# H-00491_-_Top.net
KiCad netlist of a schematic drawn in Altium Designer
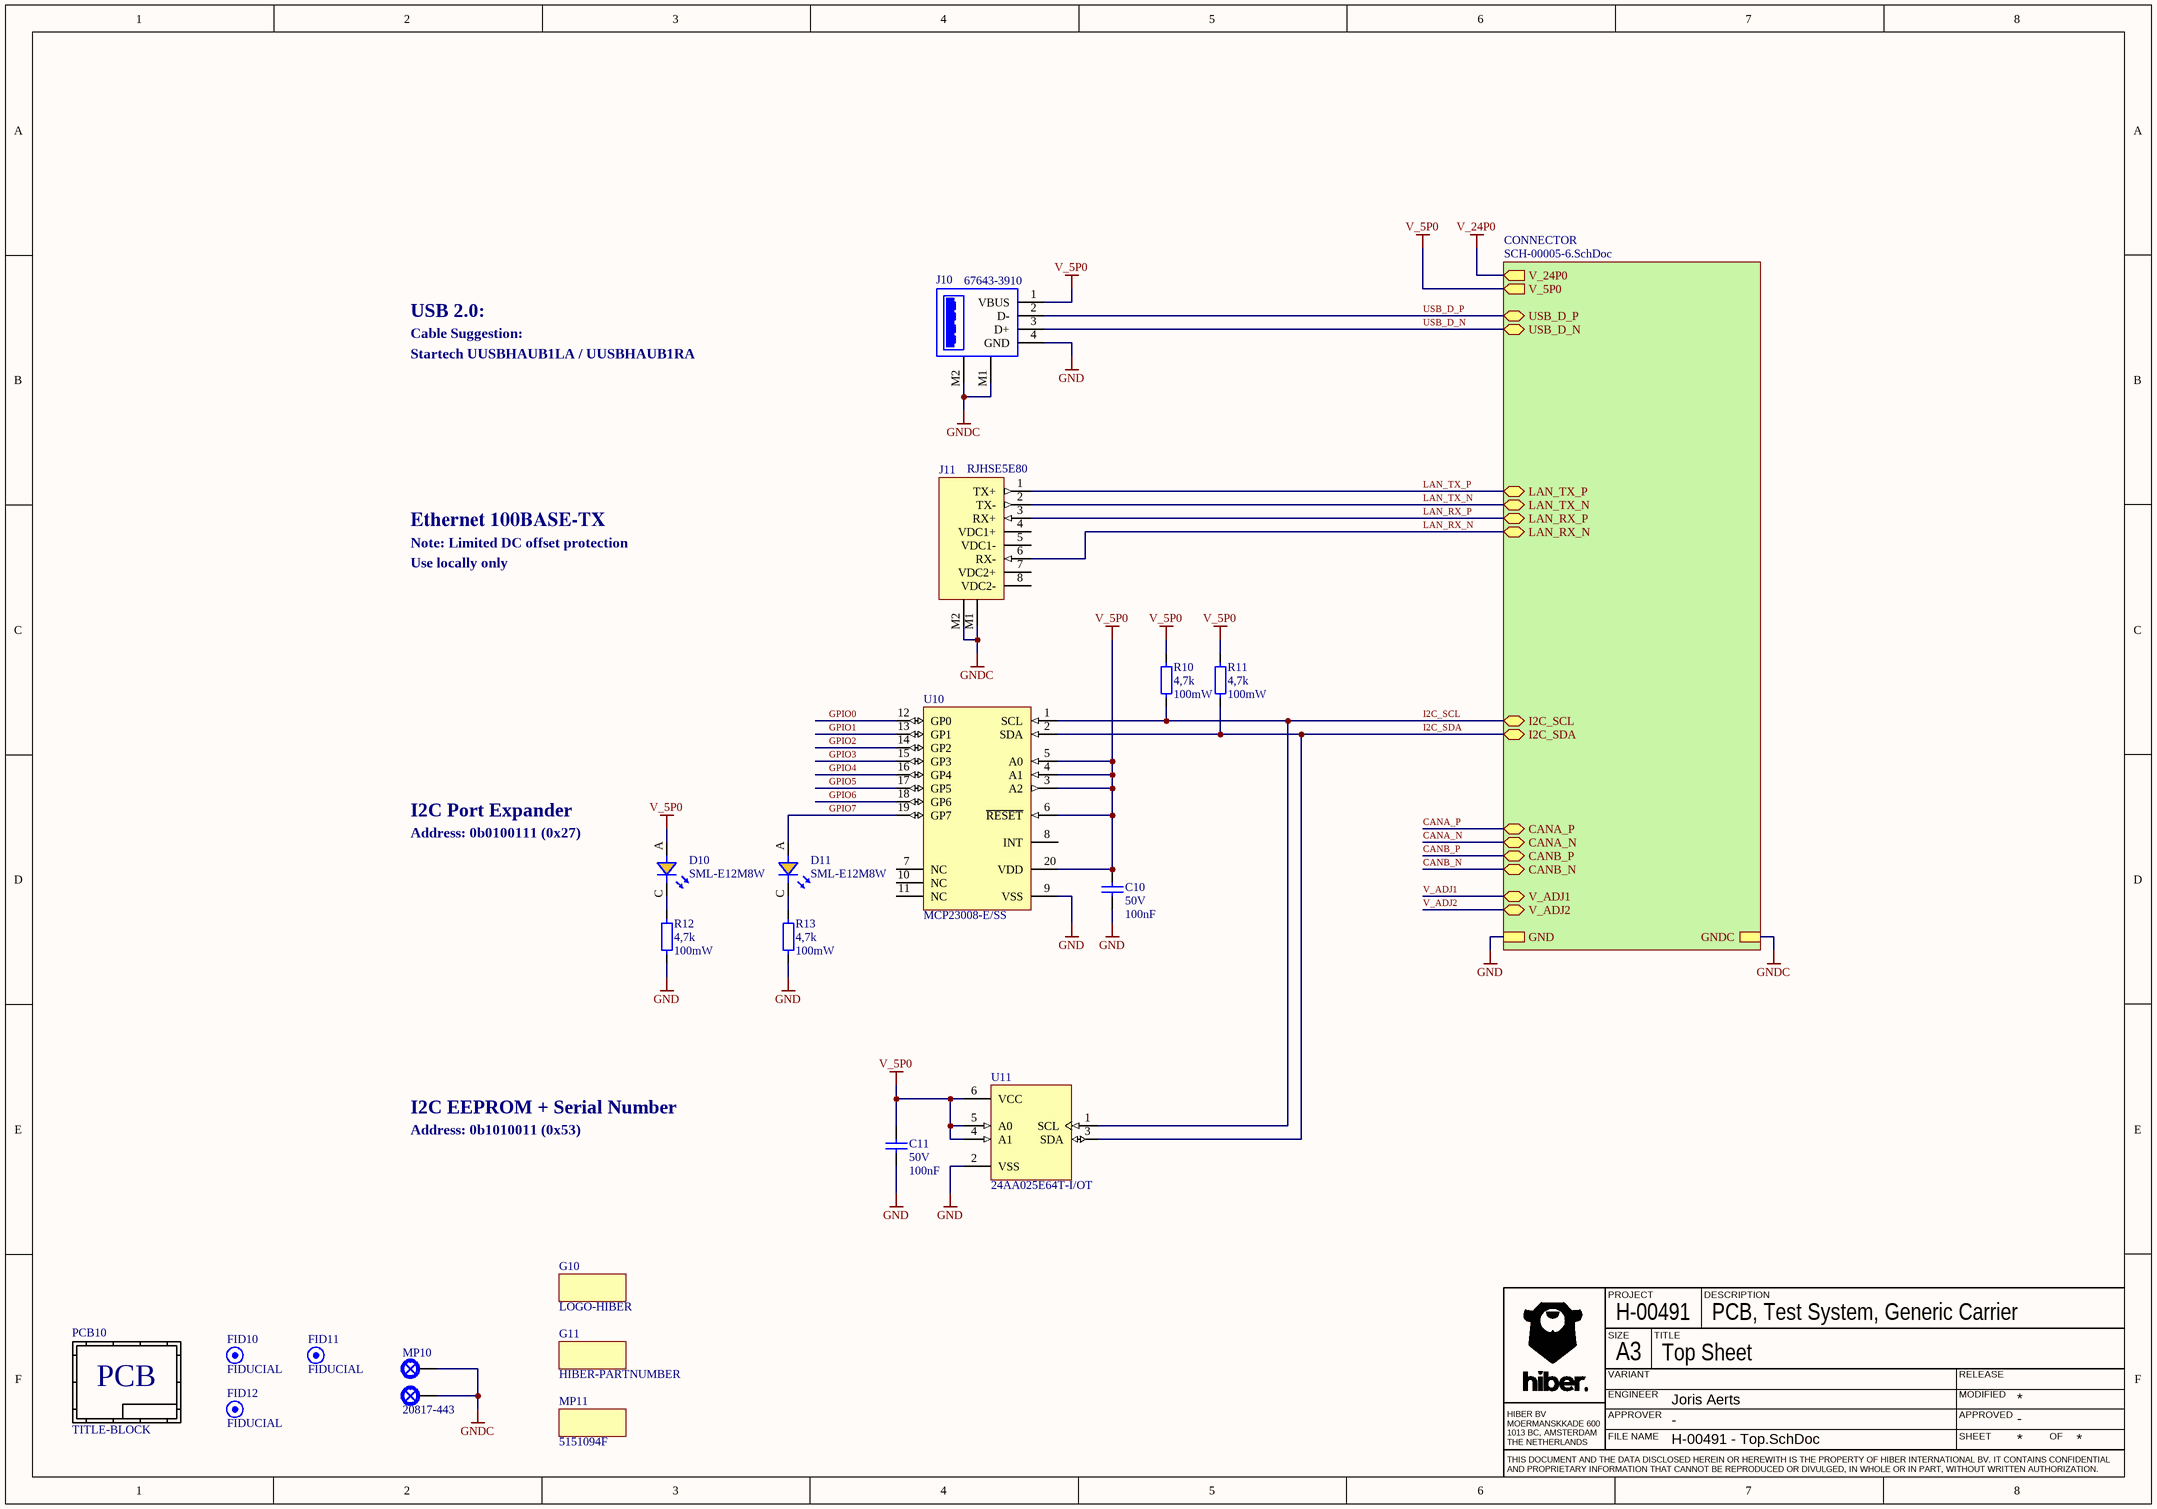
[diagram p0: H-00491 - Top.SchDoc]

(export (version "E")
  (design (tool "Eeschema 10.0.6"))
  (components
    (comp (ref "C10")
      (value "100nF")
      (footprint "CAPC160X80X87L35N")
      (description "CAP Standard 0603 (1608) 100,0nF 50V X7R (Standard)")
      (fields
        (field (name "RATED VOLTAGE") "50V")
        (field (name "TOLERANCE") "10%")
        (field (name "Comment") "C0603C104K5RACTU")
      )
      (libsource (lib "Hiber") (part "CAPACITOR"))
    )
    (comp (ref "C11")
      (value "100nF")
      (footprint "CAPC160X80X87L35N")
      (description "CAP Standard 0603 (1608) 100,0nF 50V X7R (Standard)")
      (fields
        (field (name "RATED VOLTAGE") "50V")
        (field (name "TOLERANCE") "10%")
        (field (name "Comment") "C0603C104K5RACTU")
      )
      (libsource (lib "Hiber") (part "CAPACITOR"))
    )
    (comp (ref "D10")
      (value "SML-E12M8W")
      (footprint "LEDC170X80X80L20_YELLOW")
      (description "LED Yellowish green Diffused 0603 SMD")
      (libsource (lib "Hiber") (part "DIODE-LED-YELLOW"))
    )
    (comp (ref "D11")
      (value "SML-E12M8W")
      (footprint "LEDC170X80X80L20_YELLOW")
      (description "LED Yellowish green Diffused 0603 SMD")
      (libsource (lib "Hiber") (part "DIODE-LED-YELLOW"))
    )
    (comp (ref "FID10")
      (value "FIDUCIAL")
      (footprint "FIDUCIAL_075X150")
      (description "Fiducial")
      (libsource (lib "Hiber Vault") (part "FIDUCIAL"))
    )
    (comp (ref "FID11")
      (value "FIDUCIAL")
      (footprint "FIDUCIAL_075X150")
      (description "Fiducial")
      (libsource (lib "Hiber Vault") (part "FIDUCIAL"))
    )
    (comp (ref "FID12")
      (value "FIDUCIAL")
      (footprint "FIDUCIAL_075X150")
      (description "Fiducial")
      (libsource (lib "Hiber Vault") (part "FIDUCIAL"))
    )
    (comp (ref "G10")
      (value "LOGO-HIBER")
      (footprint "HIBER_LOGO_COPPER_55x40")
      (description "Hiber Logo")
      (libsource (lib "Hiber") (part "GRAPHIC"))
    )
    (comp (ref "G11")
      (value "HIBER-PARTNUMBER")
      (footprint "HIBER_PNSN_COPPER")
      (description "Hiber Fabrication Partnumber")
      (libsource (lib "Hiber") (part "GRAPHIC"))
    )
    (comp (ref "J10")
      (value "67643-3910")
      (footprint "MOLEX_676433910")
      (description "USB Connector, 4 Contact(s), Female, Right Angle, Solder Terminal, Locking, Receptacle")
      (libsource (lib "Hiber") (part "USB-A"))
    )
    (comp (ref "J11")
      (value "RJHSE5E80")
      (footprint "AMPHENOLICC_RJHSE5E80")
      (description "Modular Connectors / Ethernet Connectors High Speed RJ w/no LEDs or Shield")
      (libsource (lib "Hiber") (part "RJHSE5E80"))
    )
    (comp (ref "MP10")
      (value "20817-443")
      (footprint "SCHROFF_20817443")
      (description "SCHROFF         20817-443             MODULE, PLUG-IN, 3U, 4HP")
      (libsource (lib "Hiber") (part "MOUNTING-HOLE-DOUBLE"))
    )
    (comp (ref "MP11")
      (value "5151094F")
      (footprint "DIALIGHT_5151094F")
      (description "Optical Pipe")
      (libsource (lib "Hiber") (part "MECHANICAL-PART"))
    )
    (comp (ref "PCB10")
      (value "TITLE-BLOCK")
      (footprint "TITLEBLOCK-A4")
      (description "Title Block and PCB BOM Line Item")
      (libsource (lib "Hiber") (part "TITLE-BLOCK"))
    )
    (comp (ref "R10")
      (value "4,7k")
      (footprint "RESC160X85X55L30N")
      (description "RES Standard Thick Film 0603 4K70 ±1% 0,1W")
      (fields
        (field (name "TOLERANCE") "1%")
        (field (name "RATED POWER") "100mW")
        (field (name "Comment") "CRCW06034K70FKEA")
      )
      (libsource (lib "Hiber") (part "RESISTOR-2P"))
    )
    (comp (ref "R11")
      (value "4,7k")
      (footprint "RESC160X85X55L30N")
      (description "RES Standard Thick Film 0603 4K70 ±1% 0,1W")
      (fields
        (field (name "TOLERANCE") "1%")
        (field (name "RATED POWER") "100mW")
        (field (name "Comment") "CRCW06034K70FKEA")
      )
      (libsource (lib "Hiber") (part "RESISTOR-2P"))
    )
    (comp (ref "R12")
      (value "4,7k")
      (footprint "RESC160X85X55L30N")
      (description "RES Standard Thick Film 0603 4K70 ±1% 0,1W")
      (fields
        (field (name "TOLERANCE") "1%")
        (field (name "RATED POWER") "100mW")
        (field (name "Comment") "CRCW06034K70FKEA")
      )
      (libsource (lib "Hiber") (part "RESISTOR-2P"))
    )
    (comp (ref "R13")
      (value "4,7k")
      (footprint "RESC160X85X55L30N")
      (description "RES Standard Thick Film 0603 4K70 ±1% 0,1W")
      (fields
        (field (name "TOLERANCE") "1%")
        (field (name "RATED POWER") "100mW")
        (field (name "Comment") "CRCW06034K70FKEA")
      )
      (libsource (lib "Hiber") (part "RESISTOR-2P"))
    )
    (comp (ref "U10")
      (value "MCP23008-E/SS")
      (footprint "SOP20P65_720X780X200L75X30N")
      (description "Parallel I/O Port, 8-Bit, 8 I/O, CMOS, PDSO20")
      (libsource (lib "Hiber") (part "PR-BUSIC-MCP23008-20"))
    )
    (comp (ref "U11")
      (value "24AA025E64T-I/OT")
      (footprint "SOT23-6P95_270X145L35X35")
      (description "EEPROM, 256X8, Serial, CMOS, PDSO5")
      (libsource (lib "Hiber") (part "MCHP-24AA025E64_025UID-SOT-23-6"))
    )
  )
  (nets
    (net (code "5") (name "/GPIO0") (class "Default")
      (node (ref "U10") (pin "12") (pinfunction "GP0_12") (pintype "bidirectional"))
    )
    (net (code "6") (name "/GPIO1") (class "Default")
      (node (ref "U10") (pin "13") (pinfunction "GP1_13") (pintype "bidirectional"))
    )
    (net (code "7") (name "/GPIO2") (class "Default")
      (node (ref "U10") (pin "14") (pinfunction "GP2_14") (pintype "bidirectional"))
    )
    (net (code "8") (name "/GPIO3") (class "Default")
      (node (ref "U10") (pin "15") (pinfunction "GP3_15") (pintype "bidirectional"))
    )
    (net (code "9") (name "/GPIO4") (class "Default")
      (node (ref "U10") (pin "16") (pinfunction "GP4_16") (pintype "bidirectional"))
    )
    (net (code "10") (name "/GPIO5") (class "Default")
      (node (ref "U10") (pin "17") (pinfunction "GP5_17") (pintype "bidirectional"))
    )
    (net (code "11") (name "/GPIO6") (class "Default")
      (node (ref "U10") (pin "18") (pinfunction "GP6_18") (pintype "bidirectional"))
    )
    (net (code "12") (name "/GPIO7") (class "Default")
      (node (ref "D11") (pin "A") (pinfunction "A_A") (pintype "passive"))
      (node (ref "U10") (pin "19") (pinfunction "GP7_19") (pintype "bidirectional"))
    )
    (net (code "13") (name "/I2C_SCL") (class "Default")
      (node (ref "R10") (pin "2") (pinfunction "2_2") (pintype "passive"))
      (node (ref "U10") (pin "1") (pinfunction "SCL_1") (pintype "input"))
      (node (ref "U11") (pin "1") (pinfunction "SCL_1") (pintype "input"))
    )
    (net (code "14") (name "/I2C_SDA") (class "Default")
      (node (ref "R11") (pin "2") (pinfunction "2_2") (pintype "passive"))
      (node (ref "U10") (pin "2") (pinfunction "SDA_2") (pintype "input"))
      (node (ref "U11") (pin "3") (pinfunction "SDA_3") (pintype "bidirectional"))
    )
    (net (code "15") (name "/LAN_RX_N") (class "Default")
      (node (ref "J11") (pin "6") (pinfunction "RX-_6") (pintype "input"))
    )
    (net (code "16") (name "/LAN_RX_P") (class "Default")
      (node (ref "J11") (pin "3") (pinfunction "RX+_3") (pintype "input"))
    )
    (net (code "17") (name "/LAN_TX_N") (class "Default")
      (node (ref "J11") (pin "2") (pinfunction "TX-_2") (pintype "output"))
    )
    (net (code "18") (name "/LAN_TX_P") (class "Default")
      (node (ref "J11") (pin "1") (pinfunction "TX+_1") (pintype "output"))
    )
    (net (code "19") (name "/USB_D_N") (class "Default")
      (node (ref "J10") (pin "3") (pinfunction "D+_3") (pintype "passive"))
    )
    (net (code "20") (name "/USB_D_P") (class "Default")
      (node (ref "J10") (pin "2") (pinfunction "D-_2") (pintype "passive"))
    )
    (net (code "23") (name "GND") (class "Default")
      (node (ref "C10") (pin "2") (pinfunction "2_2") (pintype "passive"))
      (node (ref "C11") (pin "2") (pinfunction "2_2") (pintype "passive"))
      (node (ref "J10") (pin "4") (pinfunction "GND_4") (pintype "passive"))
      (node (ref "R12") (pin "2") (pinfunction "2_2") (pintype "passive"))
      (node (ref "R13") (pin "2") (pinfunction "2_2") (pintype "passive"))
      (node (ref "U10") (pin "9") (pinfunction "VSS_9") (pintype "power_in"))
      (node (ref "U11") (pin "2") (pinfunction "VSS_2") (pintype "power_in"))
    )
    (net (code "24") (name "GNDC") (class "Default")
      (node (ref "J10") (pin "M1") (pinfunction "SHLD1_M1") (pintype "passive"))
      (node (ref "J10") (pin "M2") (pinfunction "SHLD2_M2") (pintype "passive"))
      (node (ref "J11") (pin "M1") (pinfunction "SHLD_M1") (pintype "power_in"))
      (node (ref "J11") (pin "M2") (pinfunction "SHLD_M2") (pintype "power_in"))
      (node (ref "MP10") (pin "M1") (pinfunction "1_M1") (pintype "passive"))
      (node (ref "MP10") (pin "M2") (pinfunction "1_M2") (pintype "passive"))
    )
    (net (code "25") (name "Net-(D10-PadC)") (class "Default")
      (node (ref "D10") (pin "C") (pinfunction "C_C") (pintype "passive"))
      (node (ref "R12") (pin "1") (pinfunction "1_1") (pintype "passive"))
    )
    (net (code "26") (name "Net-(D11-PadC)") (class "Default")
      (node (ref "D11") (pin "C") (pinfunction "C_C") (pintype "passive"))
      (node (ref "R13") (pin "1") (pinfunction "1_1") (pintype "passive"))
    )
    (net (code "27") (name "V_5P0") (class "Default")
      (node (ref "C10") (pin "1") (pinfunction "1_1") (pintype "passive"))
      (node (ref "C11") (pin "1") (pinfunction "1_1") (pintype "passive"))
      (node (ref "D10") (pin "A") (pinfunction "A_A") (pintype "passive"))
      (node (ref "J10") (pin "1") (pinfunction "VBUS_1") (pintype "passive"))
      (node (ref "R10") (pin "1") (pinfunction "1_1") (pintype "passive"))
      (node (ref "R11") (pin "1") (pinfunction "1_1") (pintype "passive"))
      (node (ref "U10") (pin "20") (pinfunction "VDD_20") (pintype "power_in"))
      (node (ref "U10") (pin "3") (pinfunction "A2_3") (pintype "output"))
      (node (ref "U10") (pin "4") (pinfunction "A1_4") (pintype "input"))
      (node (ref "U10") (pin "5") (pinfunction "A0_5") (pintype "input"))
      (node (ref "U10") (pin "6") (pinfunction "~{RESET}_6") (pintype "input"))
      (node (ref "U11") (pin "4") (pinfunction "A1_4") (pintype "input"))
      (node (ref "U11") (pin "5") (pinfunction "A0_5") (pintype "input"))
      (node (ref "U11") (pin "6") (pinfunction "VCC_6") (pintype "power_in"))
    )
    (net (code "29") (name "unconnected-(J11-VDC1+-Pad4)") (class "Default")
      (node (ref "J11") (pin "4") (pinfunction "VDC1+_4") (pintype "power_in"))
    )
    (net (code "30") (name "unconnected-(J11-VDC1--Pad5)") (class "Default")
      (node (ref "J11") (pin "5") (pinfunction "VDC1-_5") (pintype "power_in"))
    )
    (net (code "31") (name "unconnected-(J11-VDC2+-Pad7)") (class "Default")
      (node (ref "J11") (pin "7") (pinfunction "VDC2+_7") (pintype "power_in"))
    )
    (net (code "32") (name "unconnected-(J11-VDC2--Pad8)") (class "Default")
      (node (ref "J11") (pin "8") (pinfunction "VDC2-_8") (pintype "power_in"))
    )
    (net (code "33") (name "unconnected-(U10-INT-Pad8)") (class "Default")
      (node (ref "U10") (pin "8") (pinfunction "INT_8") (pintype "open_collector"))
    )
    (net (code "34") (name "unconnected-(U10-NC-Pad7)") (class "Default")
      (node (ref "U10") (pin "7") (pinfunction "NC_7") (pintype "passive"))
    )
    (net (code "35") (name "unconnected-(U10-NC-Pad10)") (class "Default")
      (node (ref "U10") (pin "10") (pinfunction "NC_10") (pintype "passive"))
    )
    (net (code "36") (name "unconnected-(U10-NC-Pad11)") (class "Default")
      (node (ref "U10") (pin "11") (pinfunction "NC_11") (pintype "passive"))
    )
  )
)
